# Lab_4_PLCC-20-breakout.net
KiCad netlist of a schematic drawn in EAGLE
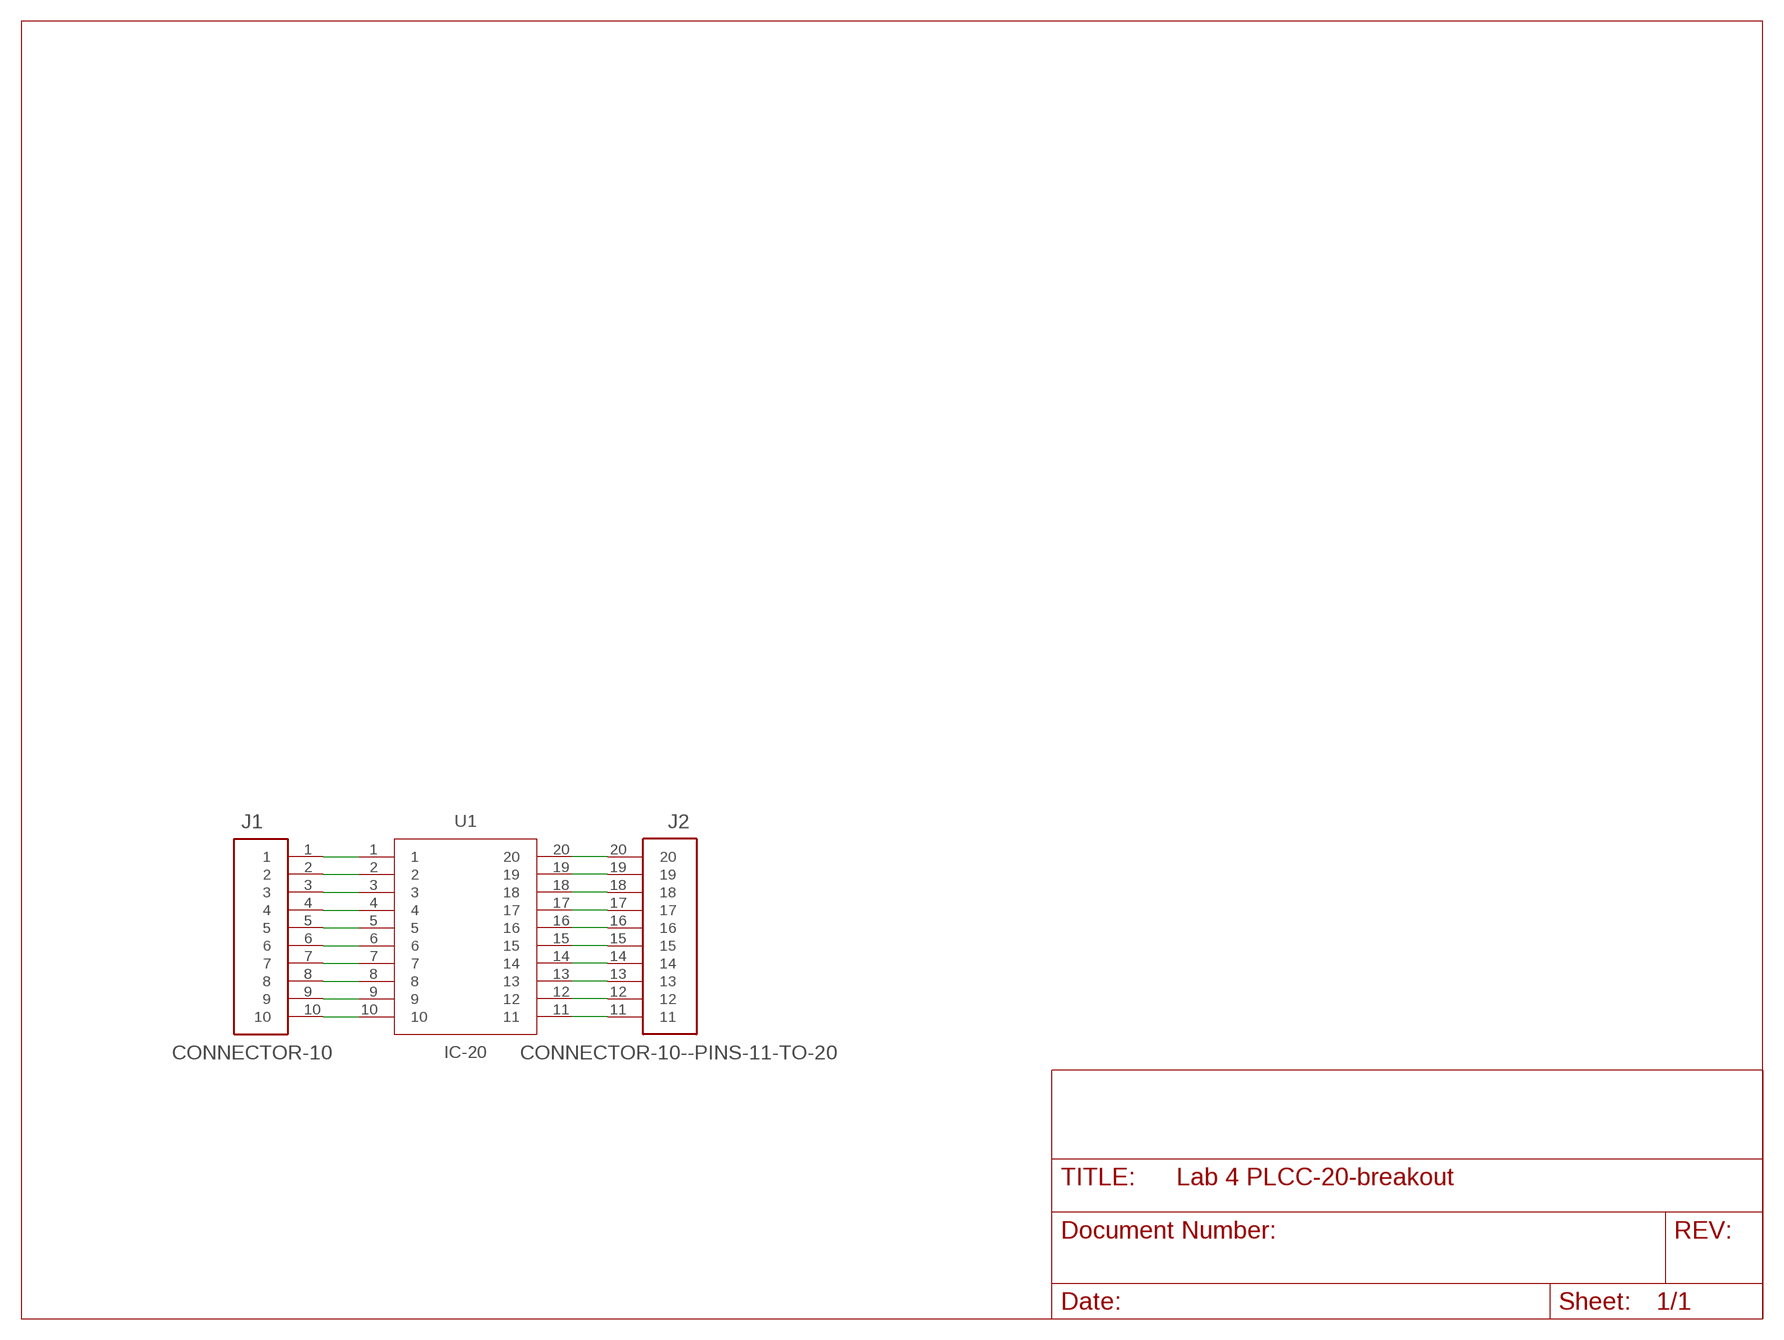
[diagram p0: schematic, sheet 1]

(export (version "E")
  (design (tool "Eeschema 10.0.6"))
  (components
    (comp (ref "J1")
      (value "CONNECTOR-10")
      (footprint "eagle-import:ESQ-110-XX-XX-S")
      (libsource (lib "eagle-import") (part "CONNECTOR-10"))
    )
    (comp (ref "J2")
      (value "CONNECTOR-10--PINS-11-TO-20")
      (footprint "eagle-import:ESQ-110-XX-XX-S--ROUND-PIN-1")
      (libsource (lib "eagle-import") (part "CONNECTOR-10--PINS-11-TO-20"))
    )
    (comp (ref "U1")
      (value "IC-20")
      (footprint "eagle-import:PLCC127P990X990X457-20N")
      (libsource (lib "eagle-import") (part "IC-20"))
    )
  )
  (nets
    (net (code "1") (name "Net-(J1-Pad1)") (class "Default")
      (node (ref "J1") (pin "1") (pinfunction "1_1") (pintype "bidirectional"))
      (node (ref "U1") (pin "1") (pinfunction "1_1") (pintype "bidirectional"))
    )
    (net (code "2") (name "Net-(J1-Pad2)") (class "Default")
      (node (ref "J1") (pin "2") (pinfunction "2_2") (pintype "bidirectional"))
      (node (ref "U1") (pin "2") (pinfunction "2_2") (pintype "bidirectional"))
    )
    (net (code "3") (name "Net-(J1-Pad3)") (class "Default")
      (node (ref "J1") (pin "3") (pinfunction "3_3") (pintype "bidirectional"))
      (node (ref "U1") (pin "3") (pinfunction "3_3") (pintype "bidirectional"))
    )
    (net (code "4") (name "Net-(J1-Pad4)") (class "Default")
      (node (ref "J1") (pin "4") (pinfunction "4_4") (pintype "bidirectional"))
      (node (ref "U1") (pin "4") (pinfunction "4_4") (pintype "bidirectional"))
    )
    (net (code "5") (name "Net-(J1-Pad5)") (class "Default")
      (node (ref "J1") (pin "5") (pinfunction "5_5") (pintype "bidirectional"))
      (node (ref "U1") (pin "5") (pinfunction "5_5") (pintype "bidirectional"))
    )
    (net (code "6") (name "Net-(J1-Pad6)") (class "Default")
      (node (ref "J1") (pin "6") (pinfunction "6_6") (pintype "bidirectional"))
      (node (ref "U1") (pin "6") (pinfunction "6_6") (pintype "bidirectional"))
    )
    (net (code "7") (name "Net-(J1-Pad7)") (class "Default")
      (node (ref "J1") (pin "7") (pinfunction "7_7") (pintype "bidirectional"))
      (node (ref "U1") (pin "7") (pinfunction "7_7") (pintype "bidirectional"))
    )
    (net (code "8") (name "Net-(J1-Pad8)") (class "Default")
      (node (ref "J1") (pin "8") (pinfunction "8_8") (pintype "bidirectional"))
      (node (ref "U1") (pin "8") (pinfunction "8_8") (pintype "bidirectional"))
    )
    (net (code "9") (name "Net-(J1-Pad9)") (class "Default")
      (node (ref "J1") (pin "9") (pinfunction "9_9") (pintype "bidirectional"))
      (node (ref "U1") (pin "9") (pinfunction "9_9") (pintype "bidirectional"))
    )
    (net (code "10") (name "Net-(J1-Pad10)") (class "Default")
      (node (ref "J1") (pin "10") (pinfunction "10_10") (pintype "bidirectional"))
      (node (ref "U1") (pin "10") (pinfunction "10_10") (pintype "bidirectional"))
    )
    (net (code "11") (name "Net-(J2-Pad11)") (class "Default")
      (node (ref "J2") (pin "11") (pinfunction "11_11") (pintype "bidirectional"))
      (node (ref "U1") (pin "11") (pinfunction "11_11") (pintype "bidirectional"))
    )
    (net (code "12") (name "Net-(J2-Pad12)") (class "Default")
      (node (ref "J2") (pin "12") (pinfunction "12_12") (pintype "bidirectional"))
      (node (ref "U1") (pin "12") (pinfunction "12_12") (pintype "bidirectional"))
    )
    (net (code "13") (name "Net-(J2-Pad13)") (class "Default")
      (node (ref "J2") (pin "13") (pinfunction "13_13") (pintype "bidirectional"))
      (node (ref "U1") (pin "13") (pinfunction "13_13") (pintype "bidirectional"))
    )
    (net (code "14") (name "Net-(J2-Pad14)") (class "Default")
      (node (ref "J2") (pin "14") (pinfunction "14_14") (pintype "bidirectional"))
      (node (ref "U1") (pin "14") (pinfunction "14_14") (pintype "bidirectional"))
    )
    (net (code "15") (name "Net-(J2-Pad15)") (class "Default")
      (node (ref "J2") (pin "15") (pinfunction "15_15") (pintype "bidirectional"))
      (node (ref "U1") (pin "15") (pinfunction "15_15") (pintype "bidirectional"))
    )
    (net (code "16") (name "Net-(J2-Pad16)") (class "Default")
      (node (ref "J2") (pin "16") (pinfunction "16_16") (pintype "bidirectional"))
      (node (ref "U1") (pin "16") (pinfunction "16_16") (pintype "bidirectional"))
    )
    (net (code "17") (name "Net-(J2-Pad17)") (class "Default")
      (node (ref "J2") (pin "17") (pinfunction "17_17") (pintype "bidirectional"))
      (node (ref "U1") (pin "17") (pinfunction "17_17") (pintype "bidirectional"))
    )
    (net (code "18") (name "Net-(J2-Pad18)") (class "Default")
      (node (ref "J2") (pin "18") (pinfunction "18_18") (pintype "bidirectional"))
      (node (ref "U1") (pin "18") (pinfunction "18_18") (pintype "bidirectional"))
    )
    (net (code "19") (name "Net-(J2-Pad19)") (class "Default")
      (node (ref "J2") (pin "19") (pinfunction "19_19") (pintype "bidirectional"))
      (node (ref "U1") (pin "19") (pinfunction "19_19") (pintype "bidirectional"))
    )
    (net (code "20") (name "Net-(J2-Pad20)") (class "Default")
      (node (ref "J2") (pin "20") (pinfunction "20_20") (pintype "bidirectional"))
      (node (ref "U1") (pin "20") (pinfunction "20_20") (pintype "bidirectional"))
    )
  )
)
